# mgnt-001.net
KiCad netlist of a schematic drawn in EAGLE
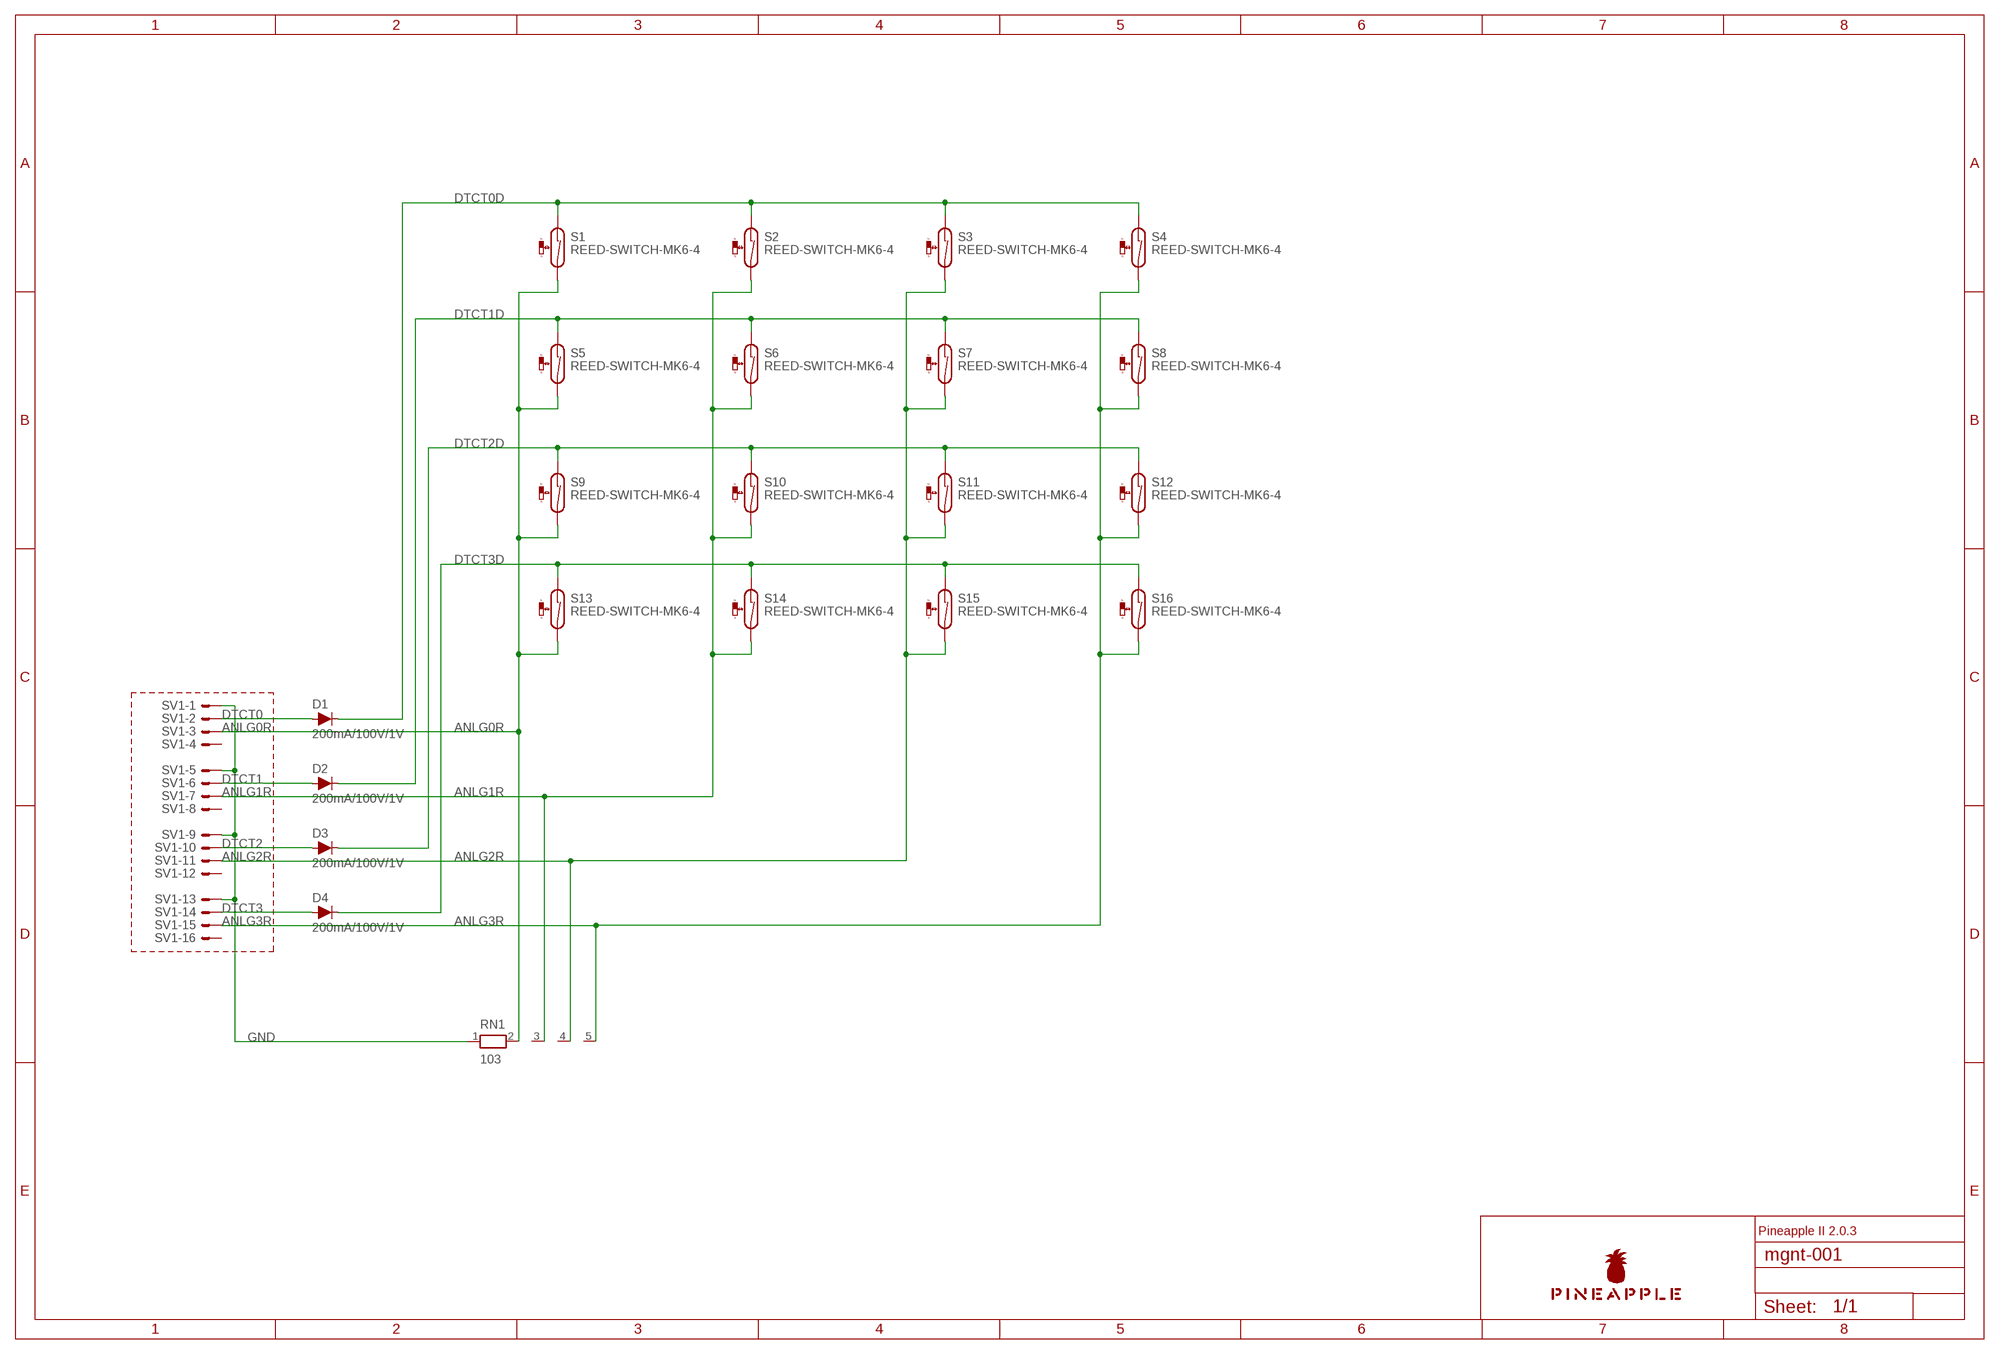
[diagram p0: schematic, sheet 1]

(export (version "E")
  (design (tool "Eeschema 10.0.6"))
  (components
    (comp (ref "D1")
      (value "200mA/100V/1V")
      (footprint "eagle-import:DIODE-1N4148")
      (libsource (lib "eagle-import") (part "DIODE-1N4148"))
    )
    (comp (ref "D2")
      (value "200mA/100V/1V")
      (footprint "eagle-import:DIODE-1N4148")
      (libsource (lib "eagle-import") (part "DIODE-1N4148"))
    )
    (comp (ref "D3")
      (value "200mA/100V/1V")
      (footprint "eagle-import:DIODE-1N4148")
      (libsource (lib "eagle-import") (part "DIODE-1N4148"))
    )
    (comp (ref "D4")
      (value "200mA/100V/1V")
      (footprint "eagle-import:DIODE-1N4148")
      (libsource (lib "eagle-import") (part "DIODE-1N4148"))
    )
    (comp (ref "RN1")
      (value "103")
      (footprint "eagle-import:RN-5")
      (libsource (lib "eagle-import") (part "RN04"))
    )
    (comp (ref "S1")
      (value "REED-SWITCH-MK6-4")
      (footprint "eagle-import:MK6-4")
      (libsource (lib "eagle-import") (part "REED-SWITCH-MK6-4"))
    )
    (comp (ref "S2")
      (value "REED-SWITCH-MK6-4")
      (footprint "eagle-import:MK6-4")
      (libsource (lib "eagle-import") (part "REED-SWITCH-MK6-4"))
    )
    (comp (ref "S3")
      (value "REED-SWITCH-MK6-4")
      (footprint "eagle-import:MK6-4")
      (libsource (lib "eagle-import") (part "REED-SWITCH-MK6-4"))
    )
    (comp (ref "S4")
      (value "REED-SWITCH-MK6-4")
      (footprint "eagle-import:MK6-4")
      (libsource (lib "eagle-import") (part "REED-SWITCH-MK6-4"))
    )
    (comp (ref "S5")
      (value "REED-SWITCH-MK6-4")
      (footprint "eagle-import:MK6-4")
      (libsource (lib "eagle-import") (part "REED-SWITCH-MK6-4"))
    )
    (comp (ref "S6")
      (value "REED-SWITCH-MK6-4")
      (footprint "eagle-import:MK6-4")
      (libsource (lib "eagle-import") (part "REED-SWITCH-MK6-4"))
    )
    (comp (ref "S7")
      (value "REED-SWITCH-MK6-4")
      (footprint "eagle-import:MK6-4")
      (libsource (lib "eagle-import") (part "REED-SWITCH-MK6-4"))
    )
    (comp (ref "S8")
      (value "REED-SWITCH-MK6-4")
      (footprint "eagle-import:MK6-4")
      (libsource (lib "eagle-import") (part "REED-SWITCH-MK6-4"))
    )
    (comp (ref "S9")
      (value "REED-SWITCH-MK6-4")
      (footprint "eagle-import:MK6-4")
      (libsource (lib "eagle-import") (part "REED-SWITCH-MK6-4"))
    )
    (comp (ref "S10")
      (value "REED-SWITCH-MK6-4")
      (footprint "eagle-import:MK6-4")
      (libsource (lib "eagle-import") (part "REED-SWITCH-MK6-4"))
    )
    (comp (ref "S11")
      (value "REED-SWITCH-MK6-4")
      (footprint "eagle-import:MK6-4")
      (libsource (lib "eagle-import") (part "REED-SWITCH-MK6-4"))
    )
    (comp (ref "S12")
      (value "REED-SWITCH-MK6-4")
      (footprint "eagle-import:MK6-4")
      (libsource (lib "eagle-import") (part "REED-SWITCH-MK6-4"))
    )
    (comp (ref "S13")
      (value "REED-SWITCH-MK6-4")
      (footprint "eagle-import:MK6-4")
      (libsource (lib "eagle-import") (part "REED-SWITCH-MK6-4"))
    )
    (comp (ref "S14")
      (value "REED-SWITCH-MK6-4")
      (footprint "eagle-import:MK6-4")
      (libsource (lib "eagle-import") (part "REED-SWITCH-MK6-4"))
    )
    (comp (ref "S15")
      (value "REED-SWITCH-MK6-4")
      (footprint "eagle-import:MK6-4")
      (libsource (lib "eagle-import") (part "REED-SWITCH-MK6-4"))
    )
    (comp (ref "S16")
      (value "REED-SWITCH-MK6-4")
      (footprint "eagle-import:MK6-4")
      (libsource (lib "eagle-import") (part "REED-SWITCH-MK6-4"))
    )
    (comp (ref "SV1")
      (value "ML16LE")
      (footprint "eagle-import:ML16L")
      (libsource (lib "eagle-import") (part "ML16LE"))
    )
    (comp (ref "U$1")
      (value "PINEAPPLELOGO2")
      (footprint "eagle-import:PINEAPPLELOGO2")
      (libsource (lib "eagle-import") (part "PINEAPPLELOGO2"))
    )
  )
  (nets
    (net (code "1") (name "/ANLG0R") (class "Default")
      (node (ref "RN1") (pin "2") (pinfunction "2_2") (pintype "passive"))
      (node (ref "S1") (pin "2") (pinfunction "2_2") (pintype "passive"))
      (node (ref "S13") (pin "2") (pinfunction "2_2") (pintype "passive"))
      (node (ref "S5") (pin "2") (pinfunction "2_2") (pintype "passive"))
      (node (ref "S9") (pin "2") (pinfunction "2_2") (pintype "passive"))
      (node (ref "SV1") (pin "3") (pinfunction "S_3") (pintype "passive"))
    )
    (net (code "2") (name "/ANLG1R") (class "Default")
      (node (ref "RN1") (pin "3") (pinfunction "3_3") (pintype "passive"))
      (node (ref "S10") (pin "2") (pinfunction "2_2") (pintype "passive"))
      (node (ref "S14") (pin "2") (pinfunction "2_2") (pintype "passive"))
      (node (ref "S2") (pin "2") (pinfunction "2_2") (pintype "passive"))
      (node (ref "S6") (pin "2") (pinfunction "2_2") (pintype "passive"))
      (node (ref "SV1") (pin "7") (pinfunction "S_7") (pintype "passive"))
    )
    (net (code "3") (name "/ANLG2R") (class "Default")
      (node (ref "RN1") (pin "4") (pinfunction "4_4") (pintype "passive"))
      (node (ref "S11") (pin "2") (pinfunction "2_2") (pintype "passive"))
      (node (ref "S15") (pin "2") (pinfunction "2_2") (pintype "passive"))
      (node (ref "S3") (pin "2") (pinfunction "2_2") (pintype "passive"))
      (node (ref "S7") (pin "2") (pinfunction "2_2") (pintype "passive"))
      (node (ref "SV1") (pin "11") (pinfunction "S_11") (pintype "passive"))
    )
    (net (code "4") (name "/ANLG3R") (class "Default")
      (node (ref "RN1") (pin "5") (pinfunction "5_5") (pintype "passive"))
      (node (ref "S12") (pin "2") (pinfunction "2_2") (pintype "passive"))
      (node (ref "S16") (pin "2") (pinfunction "2_2") (pintype "passive"))
      (node (ref "S4") (pin "2") (pinfunction "2_2") (pintype "passive"))
      (node (ref "S8") (pin "2") (pinfunction "2_2") (pintype "passive"))
      (node (ref "SV1") (pin "15") (pinfunction "S_15") (pintype "passive"))
    )
    (net (code "5") (name "/DTCT0") (class "Default")
      (node (ref "D1") (pin "A") (pinfunction "A_A") (pintype "passive"))
      (node (ref "SV1") (pin "2") (pinfunction "S_2") (pintype "passive"))
    )
    (net (code "6") (name "/DTCT0D") (class "Default")
      (node (ref "D1") (pin "C") (pinfunction "C_C") (pintype "passive"))
      (node (ref "S1") (pin "1") (pinfunction "1_1") (pintype "passive"))
      (node (ref "S2") (pin "1") (pinfunction "1_1") (pintype "passive"))
      (node (ref "S3") (pin "1") (pinfunction "1_1") (pintype "passive"))
      (node (ref "S4") (pin "1") (pinfunction "1_1") (pintype "passive"))
    )
    (net (code "7") (name "/DTCT1") (class "Default")
      (node (ref "D2") (pin "A") (pinfunction "A_A") (pintype "passive"))
      (node (ref "SV1") (pin "6") (pinfunction "S_6") (pintype "passive"))
    )
    (net (code "8") (name "/DTCT1D") (class "Default")
      (node (ref "D2") (pin "C") (pinfunction "C_C") (pintype "passive"))
      (node (ref "S5") (pin "1") (pinfunction "1_1") (pintype "passive"))
      (node (ref "S6") (pin "1") (pinfunction "1_1") (pintype "passive"))
      (node (ref "S7") (pin "1") (pinfunction "1_1") (pintype "passive"))
      (node (ref "S8") (pin "1") (pinfunction "1_1") (pintype "passive"))
    )
    (net (code "9") (name "/DTCT2") (class "Default")
      (node (ref "D3") (pin "A") (pinfunction "A_A") (pintype "passive"))
      (node (ref "SV1") (pin "10") (pinfunction "S_10") (pintype "passive"))
    )
    (net (code "10") (name "/DTCT2D") (class "Default")
      (node (ref "D3") (pin "C") (pinfunction "C_C") (pintype "passive"))
      (node (ref "S10") (pin "1") (pinfunction "1_1") (pintype "passive"))
      (node (ref "S11") (pin "1") (pinfunction "1_1") (pintype "passive"))
      (node (ref "S12") (pin "1") (pinfunction "1_1") (pintype "passive"))
      (node (ref "S9") (pin "1") (pinfunction "1_1") (pintype "passive"))
    )
    (net (code "11") (name "/DTCT3") (class "Default")
      (node (ref "D4") (pin "A") (pinfunction "A_A") (pintype "passive"))
      (node (ref "SV1") (pin "14") (pinfunction "S_14") (pintype "passive"))
    )
    (net (code "12") (name "/DTCT3D") (class "Default")
      (node (ref "D4") (pin "C") (pinfunction "C_C") (pintype "passive"))
      (node (ref "S13") (pin "1") (pinfunction "1_1") (pintype "passive"))
      (node (ref "S14") (pin "1") (pinfunction "1_1") (pintype "passive"))
      (node (ref "S15") (pin "1") (pinfunction "1_1") (pintype "passive"))
      (node (ref "S16") (pin "1") (pinfunction "1_1") (pintype "passive"))
    )
    (net (code "13") (name "/GND") (class "Default")
      (node (ref "RN1") (pin "1") (pinfunction "1_1") (pintype "passive"))
      (node (ref "SV1") (pin "1") (pinfunction "S_1") (pintype "passive"))
      (node (ref "SV1") (pin "13") (pinfunction "S_13") (pintype "passive"))
      (node (ref "SV1") (pin "5") (pinfunction "S_5") (pintype "passive"))
      (node (ref "SV1") (pin "9") (pinfunction "S_9") (pintype "passive"))
    )
    (net (code "14") (name "unconnected-(SV1D-S-Pad12)") (class "Default")
      (node (ref "SV1") (pin "12") (pinfunction "S_12") (pintype "passive"))
    )
    (net (code "15") (name "unconnected-(SV1H-S-Pad16)") (class "Default")
      (node (ref "SV1") (pin "16") (pinfunction "S_16") (pintype "passive"))
    )
    (net (code "16") (name "unconnected-(SV1K-S-Pad4)") (class "Default")
      (node (ref "SV1") (pin "4") (pinfunction "S_4") (pintype "passive"))
    )
    (net (code "17") (name "unconnected-(SV1O-S-Pad8)") (class "Default")
      (node (ref "SV1") (pin "8") (pinfunction "S_8") (pintype "passive"))
    )
  )
)
